# PCB_AirSENSE_v4_1_3.net
KiCad netlist of a schematic drawn in Altium Designer
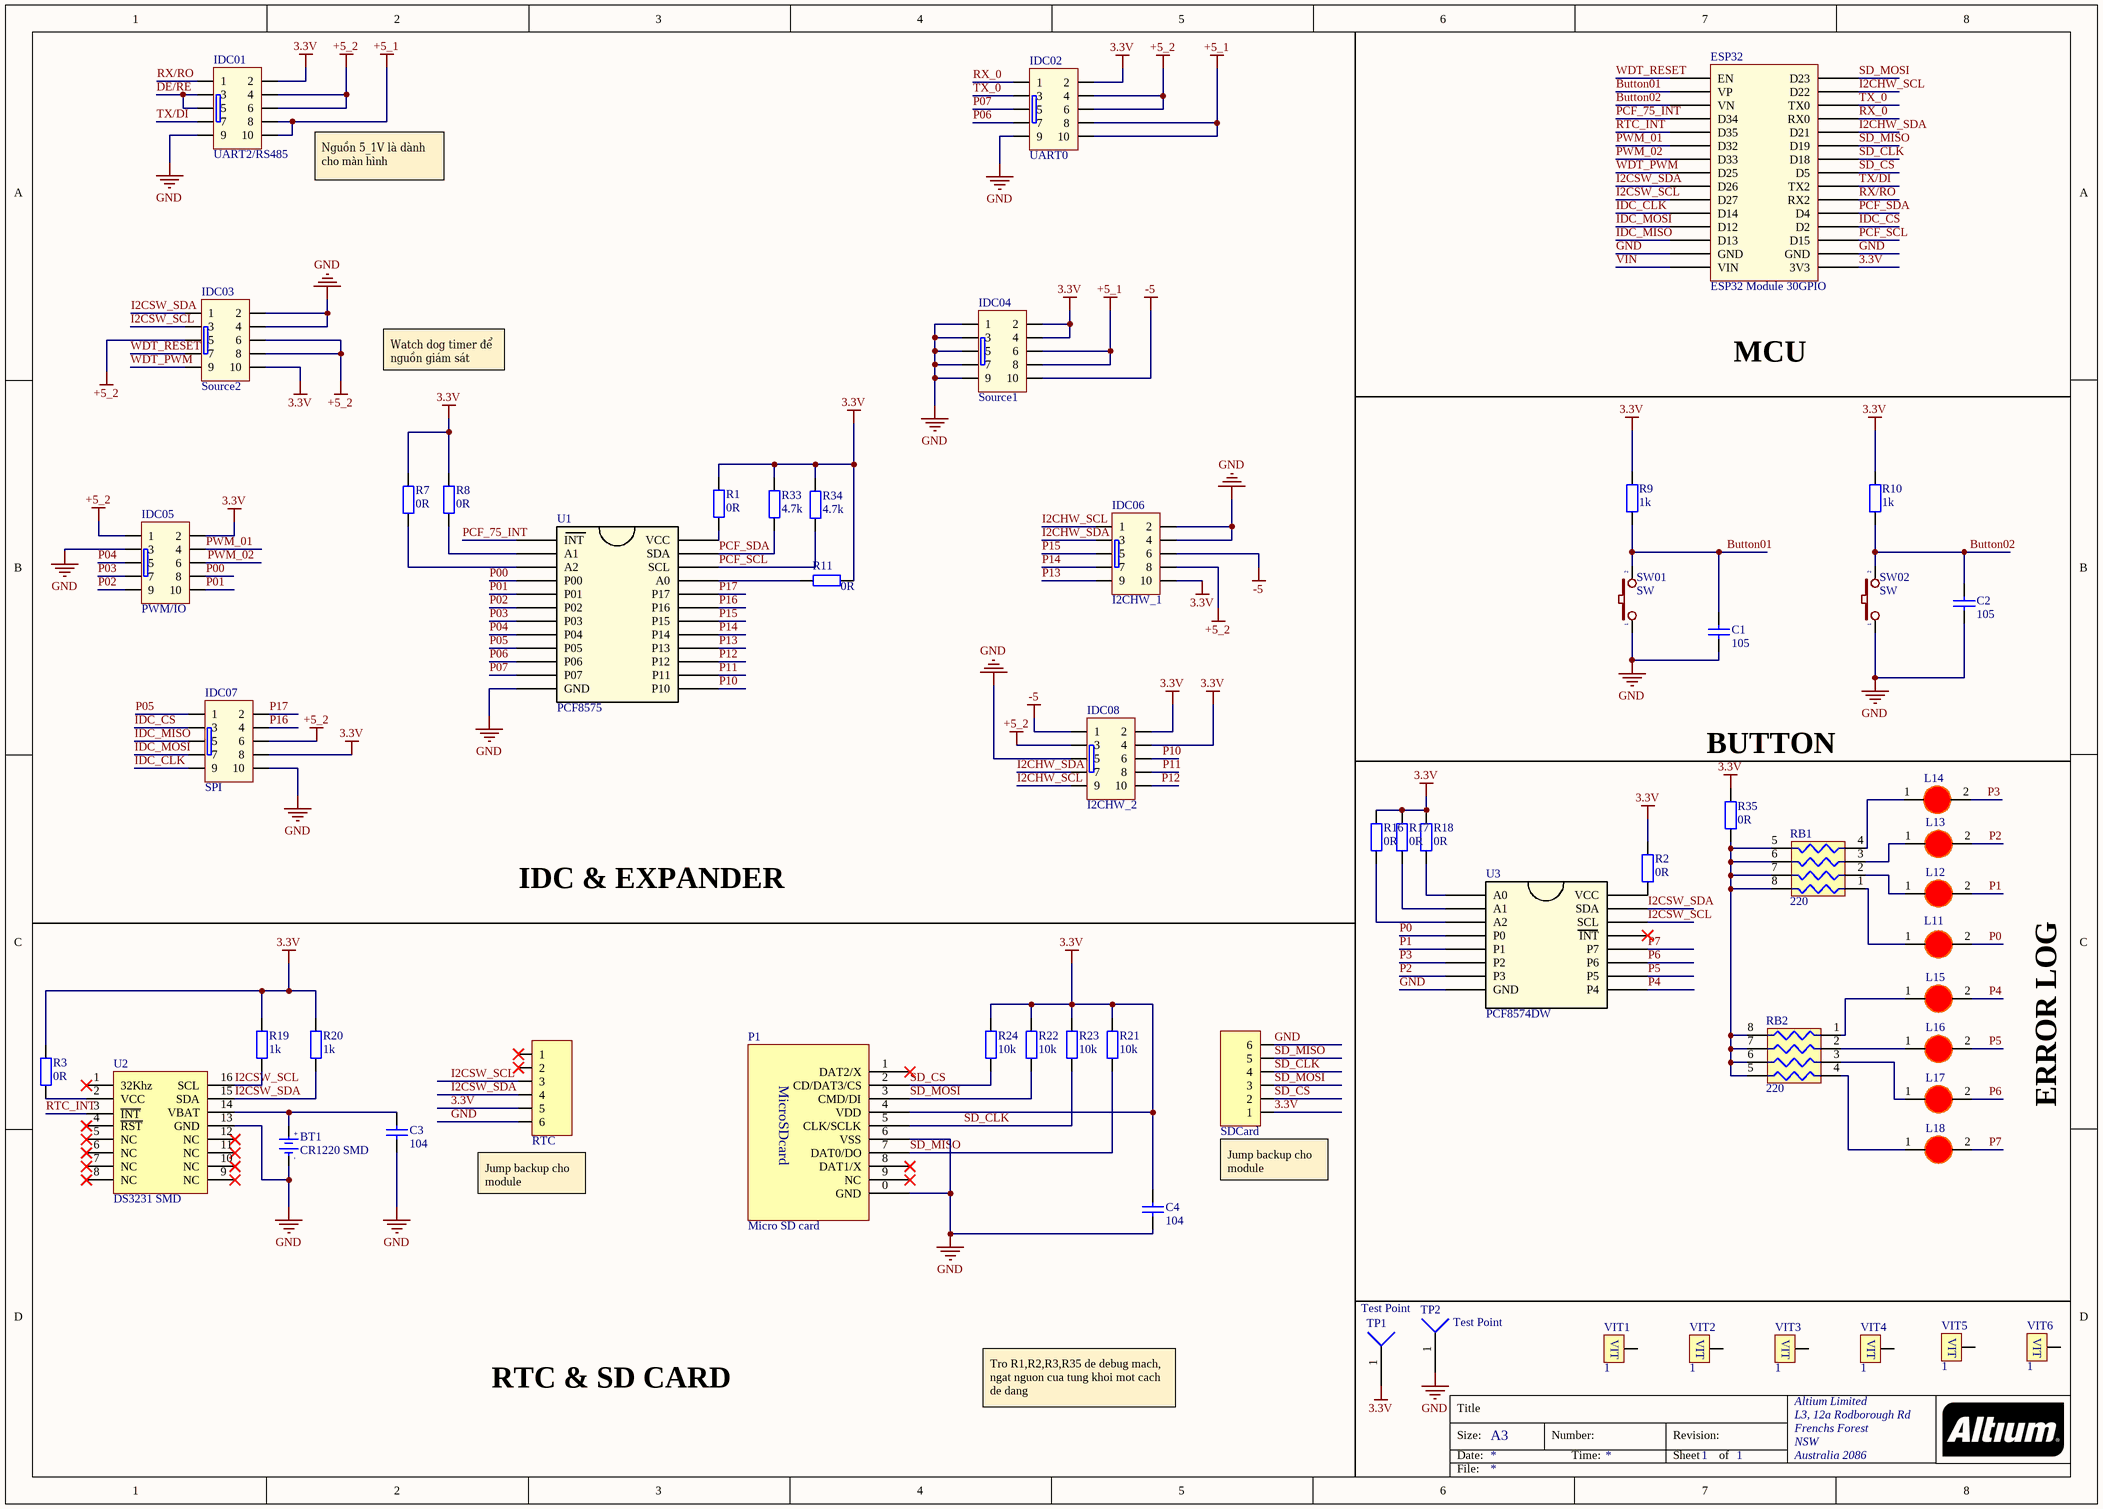
[diagram p0: PCB_AirSENSE_v4.1.3.SchDoc]

(export (version "E")
  (design (tool "Eeschema 10.0.6"))
  (components
    (comp (ref "BT1")
      (value "CR1220 SMD")
      (footprint "DE PIN CR1220")
      (libsource (lib "Component") (part "De pin CR1220 SMD"))
    )
    (comp (ref "C1")
      (value "105")
      (footprint "tu 0805")
      (description "Dán")
      (libsource (lib "Tu dien") (part "Tu 0805 105 50V 10%"))
    )
    (comp (ref "C2")
      (value "105")
      (footprint "tu 0805")
      (description "Dán")
      (libsource (lib "Tu dien") (part "Tu 0805 105 50V 10%"))
    )
    (comp (ref "C3")
      (value "104")
      (footprint "tu 0805")
      (description "Dán")
      (libsource (lib "Tu dien") (part "Tu 0805 105 50V 10%"))
    )
    (comp (ref "C4")
      (value "104")
      (footprint "tu 0805")
      (description "Dán")
      (libsource (lib "Tu dien") (part "Tu 0805 105 50V 10%"))
    )
    (comp (ref "ESP32")
      (value "ESP32 Module 30GPIO")
      (footprint "ESP32 Module 30GPIO_v3")
      (libsource (lib "Module1") (part "ESP32 Module 30GPIO"))
    )
    (comp (ref "IDC01")
      (value "UART2/RS485")
      (footprint "IDC10")
      (libsource (lib "LIBRARY") (part "IDC 5X2"))
    )
    (comp (ref "IDC02") (value "UART0") (footprint "IDC10") (libsource (lib "LIBRARY") (part "IDC 5X2")))
    (comp (ref "IDC03") (value "Source2") (footprint "IDC10") (libsource (lib "LIBRARY") (part "IDC 5X2")))
    (comp (ref "IDC04") (value "Source1") (footprint "IDC10") (libsource (lib "LIBRARY") (part "IDC 5X2")))
    (comp (ref "IDC05") (value "PWM/IO") (footprint "IDC10") (libsource (lib "LIBRARY") (part "IDC 5X2")))
    (comp (ref "IDC06") (value "I2CHW_1") (footprint "IDC10") (libsource (lib "LIBRARY") (part "IDC 5X2")))
    (comp (ref "IDC07") (value "SPI") (footprint "IDC10") (libsource (lib "LIBRARY") (part "IDC 5X2")))
    (comp (ref "IDC08") (value "I2CHW_2") (footprint "IDC10") (libsource (lib "LIBRARY") (part "IDC 5X2")))
    (comp (ref "JP3")
      (value "SDCard")
      (footprint "JP 1x6 DT")
      (description "Cắm")
      (libsource (lib "") (part "JP 1x6 2.54 Duc Thang_1"))
    )
    (comp (ref "JP4")
      (value "RTC")
      (footprint "JP 1x6 DT")
      (description "Cắm")
      (libsource (lib "Jump") (part "JP 1x6 2.54 Duc Thang"))
    )
    (comp (ref "L11")
      (value "LED 0805")
      (footprint "Led:LED-0805-Red")
      (description "Dán")
      (libsource (lib "Led") (part "LED 0805 Do"))
    )
    (comp (ref "L12")
      (value "LED 0805")
      (footprint "Led:LED-0805-Red")
      (description "Dán")
      (libsource (lib "Led") (part "LED 0805 Do"))
    )
    (comp (ref "L13")
      (value "LED 0805")
      (footprint "Led:LED-0805-Red")
      (description "Dán")
      (libsource (lib "Led") (part "LED 0805 Do"))
    )
    (comp (ref "L14")
      (value "LED 0805")
      (footprint "Led:LED-0805-Red")
      (description "Dán")
      (libsource (lib "Led") (part "LED 0805 Do"))
    )
    (comp (ref "L15")
      (value "LED 0805")
      (footprint "Led:LED-0805-Red")
      (description "Dán")
      (libsource (lib "Led") (part "LED 0805 Do"))
    )
    (comp (ref "L16")
      (value "LED 0805")
      (footprint "Led:LED-0805-Red")
      (description "Dán")
      (libsource (lib "Led") (part "LED 0805 Do"))
    )
    (comp (ref "L17")
      (value "LED 0805")
      (footprint "Led:LED-0805-Red")
      (description "Dán")
      (libsource (lib "Led") (part "LED 0805 Do"))
    )
    (comp (ref "L18")
      (value "LED 0805")
      (footprint "Led:LED-0805-Red")
      (description "Dán")
      (libsource (lib "Led") (part "LED 0805 Do"))
    )
    (comp (ref "P1")
      (value "Micro SD card")
      (footprint "MicroSD")
      (libsource (lib "Component") (part "Micro SD card"))
    )
    (comp (ref "R1")
      (value "0R")
      (footprint "tro smd 0805")
      (description "Dán")
      (libsource (lib "Dien Tro") (part "Tro 0805 5% 0R"))
    )
    (comp (ref "R2")
      (value "0R")
      (footprint "tro smd 0805")
      (description "Dán")
      (libsource (lib "Dien Tro") (part "Tro 0805 5% 0R"))
    )
    (comp (ref "R3")
      (value "0R")
      (footprint "tro smd 0805")
      (description "Dán")
      (libsource (lib "Dien Tro") (part "Tro 0805 5% 0R"))
    )
    (comp (ref "R7")
      (value "0R")
      (footprint "tro smd 0805")
      (description "Dán")
      (libsource (lib "Dien Tro") (part "Tro 0805 5% 0R"))
    )
    (comp (ref "R8")
      (value "0R")
      (footprint "tro smd 0805")
      (description "Dán")
      (libsource (lib "Dien Tro") (part "Tro 0805 5% 0R"))
    )
    (comp (ref "R9")
      (value "1k")
      (footprint "tro smd 0805")
      (description "Dán")
      (libsource (lib "Dien Tro") (part "Tro 0805 5% 0R"))
    )
    (comp (ref "R10")
      (value "1k")
      (footprint "tro smd 0805")
      (description "Dán")
      (libsource (lib "Dien Tro") (part "Tro 0805 5% 0R"))
    )
    (comp (ref "R11")
      (value "0R")
      (footprint "tro smd 0805")
      (description "Dán")
      (libsource (lib "Dien Tro") (part "Tro 0805 5% 0R"))
    )
    (comp (ref "R16")
      (value "0R")
      (footprint "tro smd 0805")
      (description "Dán")
      (libsource (lib "Dien Tro") (part "Tro 0805 5% 0R"))
    )
    (comp (ref "R17")
      (value "0R")
      (footprint "tro smd 0805")
      (description "Dán")
      (libsource (lib "Dien Tro") (part "Tro 0805 5% 0R"))
    )
    (comp (ref "R18")
      (value "0R")
      (footprint "tro smd 0805")
      (description "Dán")
      (libsource (lib "Dien Tro") (part "Tro 0805 5% 0R"))
    )
    (comp (ref "R19")
      (value "1k")
      (footprint "tro smd 0805")
      (description "Dán")
      (libsource (lib "Dien Tro") (part "Tro 0805 5% 1k"))
    )
    (comp (ref "R20")
      (value "1k")
      (footprint "tro smd 0805")
      (description "Dán")
      (libsource (lib "Dien Tro") (part "Tro 0805 5% 1k"))
    )
    (comp (ref "R21")
      (value "10k")
      (footprint "tro smd 0805")
      (description "Dán")
      (libsource (lib "Dien Tro") (part "Tro 0805 1% 10k"))
    )
    (comp (ref "R22")
      (value "10k")
      (footprint "tro smd 0805")
      (description "Dán")
      (libsource (lib "Dien Tro") (part "Tro 0805 1% 10k"))
    )
    (comp (ref "R23")
      (value "10k")
      (footprint "tro smd 0805")
      (description "Dán")
      (libsource (lib "Dien Tro") (part "Tro 0805 1% 10k"))
    )
    (comp (ref "R24")
      (value "10k")
      (footprint "tro smd 0805")
      (description "Dán")
      (libsource (lib "Dien Tro") (part "Tro 0805 1% 10k"))
    )
    (comp (ref "R33")
      (value "4.7k")
      (footprint "tro smd 0805")
      (description "Dán")
      (libsource (lib "Dien Tro") (part "Tro 0805 5% 4.7k"))
    )
    (comp (ref "R34")
      (value "4.7k")
      (footprint "tro smd 0805")
      (description "Dán")
      (libsource (lib "Dien Tro") (part "Tro 0805 5% 4.7k"))
    )
    (comp (ref "R35")
      (value "0R")
      (footprint "tro smd 0805")
      (description "Dán")
      (libsource (lib "Dien Tro") (part "Tro 0805 5% 0R"))
    )
    (comp (ref "RB1")
      (value "220")
      (footprint "tro bang 0603 4")
      (description "Dán")
      (libsource (lib "Dien Tro") (part "Tro bang 0603 220R"))
    )
    (comp (ref "RB2")
      (value "220")
      (footprint "tro bang 0603 4")
      (description "Dán")
      (libsource (lib "") (part "Tro bang 0603 220R_1"))
    )
    (comp (ref "SW01")
      (value "SW")
      (footprint "SW1-SMD")
      (description "Switch button 2 pin")
      (libsource (lib "LIBRARY") (part "SW2"))
    )
    (comp (ref "SW02")
      (value "SW")
      (footprint "SW1-SMD")
      (description "Switch button 2 pin")
      (libsource (lib "LIBRARY") (part "SW2"))
    )
    (comp (ref "TP1")
      (value "Test Point")
      (footprint "MinhTien_PCBLib:TEST_POINT_1.5X1.5MM")
      (fields (field (name "PUBLISHER") "Altium Limited"))
      (libsource (lib "MinhTien_SCHLib") (part "Test Point"))
    )
    (comp (ref "TP2")
      (value "Test Point")
      (footprint "MinhTien_PCBLib:TEST_POINT_1.5X1.5MM")
      (fields (field (name "PUBLISHER") "Altium Limited"))
      (libsource (lib "MinhTien_SCHLib") (part "Test Point"))
    )
    (comp (ref "U1")
      (value "PCF8575")
      (footprint "IC:SSOP65P775X200-24N")
      (description "PCF8575DW 24pins to expand I/O by I2C protocol (16bit)")
      (libsource (lib "IC") (part "PCF8575DW"))
    )
    (comp (ref "U2")
      (value "DS3231 SMD")
      (footprint "SOIC 16")
      (description "SOIC")
      (libsource (lib "IC") (part "DS3231 SMD"))
    )
    (comp (ref "U3")
      (value "PCF8574DW")
      (footprint "PCF8574DW SOIC16")
      (description "PCF8574DW 16 pins to expand I/O by I2C protocol (8bit)")
      (libsource (lib "IC") (part "PCF8574DW"))
    )
    (comp (ref "VIT1")
      (value "1")
      (footprint "VIT_3.7mm")
      (description "Oc Vit")
      (libsource (lib "lpson") (part "VIT"))
    )
    (comp (ref "VIT2")
      (value "1")
      (footprint "VIT_3.7mm")
      (description "Oc Vit")
      (libsource (lib "lpson") (part "VIT"))
    )
    (comp (ref "VIT3")
      (value "1")
      (footprint "VIT_3.7mm")
      (description "Oc Vit")
      (libsource (lib "lpson") (part "VIT"))
    )
    (comp (ref "VIT4")
      (value "1")
      (footprint "VIT_3.7mm")
      (description "Oc Vit")
      (libsource (lib "lpson") (part "VIT"))
    )
    (comp (ref "VIT5")
      (value "1")
      (footprint "VIT_3.7mm")
      (description "Oc Vit")
      (libsource (lib "lpson") (part "VIT"))
    )
    (comp (ref "VIT6")
      (value "1")
      (footprint "VIT_3.7mm")
      (description "Oc Vit")
      (libsource (lib "lpson") (part "VIT"))
    )
  )
  (nets
    (net (code "1") (name "+5_1") (class "Default")
      (node (ref "IDC01") (pin "10") (pinfunction "10_10") (pintype "passive"))
      (node (ref "IDC01") (pin "8") (pinfunction "8_8") (pintype "passive"))
      (node (ref "IDC02") (pin "10") (pinfunction "10_10") (pintype "passive"))
      (node (ref "IDC02") (pin "8") (pinfunction "8_8") (pintype "passive"))
      (node (ref "IDC04") (pin "6") (pinfunction "6_6") (pintype "passive"))
      (node (ref "IDC04") (pin "8") (pinfunction "8_8") (pintype "passive"))
    )
    (net (code "2") (name "+5_2") (class "Default")
      (node (ref "IDC01") (pin "4") (pinfunction "4_4") (pintype "passive"))
      (node (ref "IDC01") (pin "6") (pinfunction "6_6") (pintype "passive"))
      (node (ref "IDC02") (pin "4") (pinfunction "4_4") (pintype "passive"))
      (node (ref "IDC02") (pin "6") (pinfunction "6_6") (pintype "passive"))
      (node (ref "IDC03") (pin "5") (pinfunction "5_5") (pintype "passive"))
      (node (ref "IDC03") (pin "6") (pinfunction "6_6") (pintype "passive"))
      (node (ref "IDC03") (pin "8") (pinfunction "8_8") (pintype "passive"))
      (node (ref "IDC05") (pin "1") (pinfunction "1_1") (pintype "passive"))
      (node (ref "IDC06") (pin "8") (pinfunction "8_8") (pintype "passive"))
      (node (ref "IDC07") (pin "6") (pinfunction "6_6") (pintype "passive"))
      (node (ref "IDC08") (pin "3") (pinfunction "3_3") (pintype "passive"))
    )
    (net (code "3") (name "-5") (class "Default")
      (node (ref "IDC04") (pin "10") (pinfunction "10_10") (pintype "passive"))
      (node (ref "IDC06") (pin "6") (pinfunction "6_6") (pintype "passive"))
      (node (ref "IDC08") (pin "1") (pinfunction "1_1") (pintype "passive"))
    )
    (net (code "4") (name "/Button01") (class "Default")
      (node (ref "C1") (pin "1") (pinfunction "1_1") (pintype "passive"))
      (node (ref "ESP32") (pin "17") (pinfunction "VP_17") (pintype "passive"))
      (node (ref "R9") (pin "1") (pinfunction "1_1") (pintype "passive"))
      (node (ref "SW01") (pin "2") (pinfunction "2_2") (pintype "passive"))
    )
    (net (code "5") (name "/Button02") (class "Default")
      (node (ref "C2") (pin "1") (pinfunction "1_1") (pintype "passive"))
      (node (ref "ESP32") (pin "18") (pinfunction "VN_18") (pintype "passive"))
      (node (ref "R10") (pin "1") (pinfunction "1_1") (pintype "passive"))
      (node (ref "SW02") (pin "2") (pinfunction "2_2") (pintype "passive"))
    )
    (net (code "6") (name "/DE{slash}RE") (class "Default")
      (node (ref "IDC01") (pin "3") (pinfunction "3_3") (pintype "passive"))
      (node (ref "IDC01") (pin "5") (pinfunction "5_5") (pintype "passive"))
    )
    (net (code "7") (name "/I2CHW_SCL") (class "Default")
      (node (ref "ESP32") (pin "2") (pinfunction "D22_2") (pintype "passive"))
      (node (ref "IDC06") (pin "1") (pinfunction "1_1") (pintype "passive"))
      (node (ref "IDC08") (pin "9") (pinfunction "9_9") (pintype "passive"))
    )
    (net (code "8") (name "/I2CHW_SDA") (class "Default")
      (node (ref "ESP32") (pin "5") (pinfunction "D21_5") (pintype "passive"))
      (node (ref "IDC06") (pin "3") (pinfunction "3_3") (pintype "passive"))
      (node (ref "IDC08") (pin "7") (pinfunction "7_7") (pintype "passive"))
    )
    (net (code "9") (name "/I2CSW_SCL") (class "Default")
      (node (ref "ESP32") (pin "25") (pinfunction "D27_25") (pintype "passive"))
      (node (ref "IDC03") (pin "3") (pinfunction "3_3") (pintype "passive"))
      (node (ref "JP4") (pin "3") (pinfunction "3_3") (pintype "passive"))
      (node (ref "R19") (pin "1") (pinfunction "1_1") (pintype "passive"))
      (node (ref "U2") (pin "16") (pinfunction "SCL_16") (pintype "power_in"))
      (node (ref "U3") (pin "14") (pinfunction "SCL_14") (pintype "passive"))
    )
    (net (code "10") (name "/I2CSW_SDA") (class "Default")
      (node (ref "ESP32") (pin "24") (pinfunction "D26_24") (pintype "passive"))
      (node (ref "IDC03") (pin "1") (pinfunction "1_1") (pintype "passive"))
      (node (ref "JP4") (pin "4") (pinfunction "4_4") (pintype "passive"))
      (node (ref "R20") (pin "1") (pinfunction "1_1") (pintype "passive"))
      (node (ref "U2") (pin "15") (pinfunction "SDA_15") (pintype "power_in"))
      (node (ref "U3") (pin "15") (pinfunction "SDA_15") (pintype "passive"))
    )
    (net (code "11") (name "/IDC_CLK") (class "Default")
      (node (ref "ESP32") (pin "26") (pinfunction "D14_26") (pintype "passive"))
      (node (ref "IDC07") (pin "9") (pinfunction "9_9") (pintype "passive"))
    )
    (net (code "12") (name "/IDC_CS") (class "Default")
      (node (ref "ESP32") (pin "12") (pinfunction "D2_12") (pintype "passive"))
      (node (ref "IDC07") (pin "3") (pinfunction "3_3") (pintype "passive"))
    )
    (net (code "13") (name "/IDC_MISO") (class "Default")
      (node (ref "ESP32") (pin "28") (pinfunction "D13_28") (pintype "passive"))
      (node (ref "IDC07") (pin "5") (pinfunction "5_5") (pintype "passive"))
    )
    (net (code "14") (name "/IDC_MOSI") (class "Default")
      (node (ref "ESP32") (pin "27") (pinfunction "D12_27") (pintype "passive"))
      (node (ref "IDC07") (pin "7") (pinfunction "7_7") (pintype "passive"))
    )
    (net (code "15") (name "/P00") (class "Default")
      (node (ref "IDC05") (pin "8") (pinfunction "8_8") (pintype "passive"))
      (node (ref "U1") (pin "4") (pinfunction "P00_4") (pintype "passive"))
    )
    (net (code "16") (name "/P0") (class "Default")
      (node (ref "L11") (pin "2") (pinfunction "K_2") (pintype "passive"))
      (node (ref "U3") (pin "4") (pinfunction "P0_4") (pintype "passive"))
    )
    (net (code "17") (name "/P01") (class "Default")
      (node (ref "IDC05") (pin "10") (pinfunction "10_10") (pintype "passive"))
      (node (ref "U1") (pin "5") (pinfunction "P01_5") (pintype "passive"))
    )
    (net (code "18") (name "/P1") (class "Default")
      (node (ref "L12") (pin "2") (pinfunction "K_2") (pintype "passive"))
      (node (ref "U3") (pin "5") (pinfunction "P1_5") (pintype "passive"))
    )
    (net (code "19") (name "/P02") (class "Default")
      (node (ref "IDC05") (pin "9") (pinfunction "9_9") (pintype "passive"))
      (node (ref "U1") (pin "6") (pinfunction "P02_6") (pintype "passive"))
    )
    (net (code "20") (name "/P2") (class "Default")
      (node (ref "L13") (pin "2") (pinfunction "K_2") (pintype "passive"))
      (node (ref "U3") (pin "7") (pinfunction "P3_7") (pintype "passive"))
    )
    (net (code "21") (name "/P3") (class "Default")
      (node (ref "L14") (pin "2") (pinfunction "K_2") (pintype "passive"))
      (node (ref "U3") (pin "6") (pinfunction "P2_6") (pintype "passive"))
    )
    (net (code "22") (name "/P03") (class "Default")
      (node (ref "IDC05") (pin "7") (pinfunction "7_7") (pintype "passive"))
      (node (ref "U1") (pin "7") (pinfunction "P03_7") (pintype "passive"))
    )
    (net (code "23") (name "/P4") (class "Default")
      (node (ref "L15") (pin "2") (pinfunction "K_2") (pintype "passive"))
      (node (ref "U3") (pin "9") (pinfunction "P4_9") (pintype "passive"))
    )
    (net (code "24") (name "/P04") (class "Default")
      (node (ref "IDC05") (pin "5") (pinfunction "5_5") (pintype "passive"))
      (node (ref "U1") (pin "8") (pinfunction "P04_8") (pintype "passive"))
    )
    (net (code "25") (name "/P5") (class "Default")
      (node (ref "L16") (pin "2") (pinfunction "K_2") (pintype "passive"))
      (node (ref "U3") (pin "10") (pinfunction "P5_10") (pintype "passive"))
    )
    (net (code "26") (name "/P05") (class "Default")
      (node (ref "IDC07") (pin "1") (pinfunction "1_1") (pintype "passive"))
      (node (ref "U1") (pin "9") (pinfunction "P05_9") (pintype "passive"))
    )
    (net (code "27") (name "/P06") (class "Default")
      (node (ref "IDC02") (pin "7") (pinfunction "7_7") (pintype "passive"))
      (node (ref "U1") (pin "10") (pinfunction "P06_10") (pintype "passive"))
    )
    (net (code "28") (name "/P6") (class "Default")
      (node (ref "L17") (pin "2") (pinfunction "K_2") (pintype "passive"))
      (node (ref "U3") (pin "11") (pinfunction "P6_11") (pintype "passive"))
    )
    (net (code "29") (name "/P7") (class "Default")
      (node (ref "L18") (pin "2") (pinfunction "K_2") (pintype "passive"))
      (node (ref "U3") (pin "12") (pinfunction "P7_12") (pintype "passive"))
    )
    (net (code "30") (name "/P07") (class "Default")
      (node (ref "IDC02") (pin "5") (pinfunction "5_5") (pintype "passive"))
      (node (ref "U1") (pin "11") (pinfunction "P07_11") (pintype "passive"))
    )
    (net (code "31") (name "/P10") (class "Default")
      (node (ref "IDC08") (pin "6") (pinfunction "6_6") (pintype "passive"))
      (node (ref "U1") (pin "13") (pinfunction "P10_13") (pintype "passive"))
    )
    (net (code "32") (name "/P11") (class "Default")
      (node (ref "IDC08") (pin "8") (pinfunction "8_8") (pintype "passive"))
      (node (ref "U1") (pin "14") (pinfunction "P11_14") (pintype "passive"))
    )
    (net (code "33") (name "/P12") (class "Default")
      (node (ref "IDC08") (pin "10") (pinfunction "10_10") (pintype "passive"))
      (node (ref "U1") (pin "15") (pinfunction "P12_15") (pintype "passive"))
    )
    (net (code "34") (name "/P13") (class "Default")
      (node (ref "IDC06") (pin "9") (pinfunction "9_9") (pintype "passive"))
      (node (ref "U1") (pin "16") (pinfunction "P13_16") (pintype "passive"))
    )
    (net (code "35") (name "/P14") (class "Default")
      (node (ref "IDC06") (pin "7") (pinfunction "7_7") (pintype "passive"))
      (node (ref "U1") (pin "17") (pinfunction "P14_17") (pintype "passive"))
    )
    (net (code "36") (name "/P15") (class "Default")
      (node (ref "IDC06") (pin "5") (pinfunction "5_5") (pintype "passive"))
      (node (ref "U1") (pin "18") (pinfunction "P15_18") (pintype "passive"))
    )
    (net (code "37") (name "/P16") (class "Default")
      (node (ref "IDC07") (pin "4") (pinfunction "4_4") (pintype "passive"))
      (node (ref "U1") (pin "19") (pinfunction "P16_19") (pintype "passive"))
    )
    (net (code "38") (name "/P17") (class "Default")
      (node (ref "IDC07") (pin "2") (pinfunction "2_2") (pintype "passive"))
      (node (ref "U1") (pin "20") (pinfunction "P17_20") (pintype "passive"))
    )
    (net (code "39") (name "/PCF_75_INT") (class "Default")
      (node (ref "ESP32") (pin "19") (pinfunction "D34_19") (pintype "passive"))
      (node (ref "U1") (pin "1") (pinfunction "INT_1") (pintype "passive"))
    )
    (net (code "40") (name "/PCF_SCL") (class "Default")
      (node (ref "ESP32") (pin "13") (pinfunction "D15_13") (pintype "passive"))
      (node (ref "R34") (pin "1") (pinfunction "1_1") (pintype "passive"))
      (node (ref "U1") (pin "22") (pinfunction "SCL_22") (pintype "passive"))
    )
    (net (code "41") (name "/PCF_SDA") (class "Default")
      (node (ref "ESP32") (pin "11") (pinfunction "D4_11") (pintype "passive"))
      (node (ref "R33") (pin "1") (pinfunction "1_1") (pintype "passive"))
      (node (ref "U1") (pin "23") (pinfunction "SDA_23") (pintype "passive"))
    )
    (net (code "42") (name "/PWM_01") (class "Default")
      (node (ref "ESP32") (pin "21") (pinfunction "D32_21") (pintype "passive"))
      (node (ref "IDC05") (pin "4") (pinfunction "4_4") (pintype "passive"))
    )
    (net (code "43") (name "/PWM_02") (class "Default")
      (node (ref "ESP32") (pin "22") (pinfunction "D33_22") (pintype "passive"))
      (node (ref "IDC05") (pin "6") (pinfunction "6_6") (pintype "passive"))
    )
    (net (code "44") (name "/RTC_INT") (class "Default")
      (node (ref "ESP32") (pin "20") (pinfunction "D35_20") (pintype "passive"))
      (node (ref "U2") (pin "3") (pinfunction "~{INT}_3") (pintype "power_in"))
    )
    (net (code "45") (name "/RX_0") (class "Default")
      (node (ref "ESP32") (pin "4") (pinfunction "RX0_4") (pintype "passive"))
      (node (ref "IDC02") (pin "1") (pinfunction "1_1") (pintype "passive"))
    )
    (net (code "46") (name "/RX{slash}RO") (class "Default")
      (node (ref "ESP32") (pin "10") (pinfunction "RX2_10") (pintype "passive"))
      (node (ref "IDC01") (pin "1") (pinfunction "1_1") (pintype "passive"))
    )
    (net (code "47") (name "/SD_CLK") (class "Default")
      (node (ref "ESP32") (pin "7") (pinfunction "D18_7") (pintype "passive"))
      (node (ref "JP3") (pin "4") (pinfunction "4_4") (pintype "passive"))
      (node (ref "P1") (pin "5") (pinfunction "CLK/SCLK_5") (pintype "passive"))
      (node (ref "R23") (pin "1") (pinfunction "1_1") (pintype "passive"))
    )
    (net (code "48") (name "/SD_CS") (class "Default")
      (node (ref "ESP32") (pin "8") (pinfunction "D5_8") (pintype "passive"))
      (node (ref "JP3") (pin "2") (pinfunction "2_2") (pintype "passive"))
      (node (ref "P1") (pin "2") (pinfunction "CD/DAT3/CS_2") (pintype "passive"))
      (node (ref "R24") (pin "1") (pinfunction "1_1") (pintype "passive"))
    )
    (net (code "49") (name "/SD_MISO") (class "Default")
      (node (ref "ESP32") (pin "6") (pinfunction "D19_6") (pintype "passive"))
      (node (ref "JP3") (pin "5") (pinfunction "5_5") (pintype "passive"))
      (node (ref "P1") (pin "7") (pinfunction "DAT0/DO_7") (pintype "passive"))
      (node (ref "R21") (pin "1") (pinfunction "1_1") (pintype "passive"))
    )
    (net (code "50") (name "/SD_MOSI") (class "Default")
      (node (ref "ESP32") (pin "1") (pinfunction "D23_1") (pintype "passive"))
      (node (ref "JP3") (pin "3") (pinfunction "3_3") (pintype "passive"))
      (node (ref "P1") (pin "3") (pinfunction "CMD/DI_3") (pintype "passive"))
      (node (ref "R22") (pin "1") (pinfunction "1_1") (pintype "passive"))
    )
    (net (code "51") (name "/TX_0") (class "Default")
      (node (ref "ESP32") (pin "3") (pinfunction "TX0_3") (pintype "passive"))
      (node (ref "IDC02") (pin "3") (pinfunction "3_3") (pintype "passive"))
    )
    (net (code "52") (name "/TX{slash}DI") (class "Default")
      (node (ref "ESP32") (pin "9") (pinfunction "TX2_9") (pintype "passive"))
      (node (ref "IDC01") (pin "7") (pinfunction "7_7") (pintype "passive"))
    )
    (net (code "53") (name "/VIN") (class "Default")
      (node (ref "ESP32") (pin "30") (pinfunction "VIN_30") (pintype "passive"))
    )
    (net (code "54") (name "/WDT_PWM") (class "Default")
      (node (ref "ESP32") (pin "23") (pinfunction "D25_23") (pintype "passive"))
      (node (ref "IDC03") (pin "9") (pinfunction "9_9") (pintype "passive"))
    )
    (net (code "55") (name "/WDT_RESET") (class "Default")
      (node (ref "ESP32") (pin "16") (pinfunction "EN_16") (pintype "passive"))
      (node (ref "IDC03") (pin "7") (pinfunction "7_7") (pintype "passive"))
    )
    (net (code "56") (name "3.3V") (class "Default")
      (node (ref "C4") (pin "1") (pinfunction "1_1") (pintype "passive"))
      (node (ref "ESP32") (pin "15") (pinfunction "3V3_15") (pintype "passive"))
      (node (ref "IDC01") (pin "2") (pinfunction "2_2") (pintype "passive"))
      (node (ref "IDC02") (pin "2") (pinfunction "2_2") (pintype "passive"))
      (node (ref "IDC03") (pin "10") (pinfunction "10_10") (pintype "passive"))
      (node (ref "IDC04") (pin "2") (pinfunction "2_2") (pintype "passive"))
      (node (ref "IDC04") (pin "4") (pinfunction "4_4") (pintype "passive"))
      (node (ref "IDC05") (pin "2") (pinfunction "2_2") (pintype "passive"))
      (node (ref "IDC06") (pin "10") (pinfunction "10_10") (pintype "passive"))
      (node (ref "IDC07") (pin "8") (pinfunction "8_8") (pintype "passive"))
      (node (ref "IDC08") (pin "2") (pinfunction "2_2") (pintype "passive"))
      (node (ref "IDC08") (pin "4") (pinfunction "4_4") (pintype "passive"))
      (node (ref "JP3") (pin "1") (pinfunction "1_1") (pintype "passive"))
      (node (ref "JP4") (pin "5") (pinfunction "5_5") (pintype "passive"))
      (node (ref "P1") (pin "4") (pinfunction "VDD_4") (pintype "passive"))
      (node (ref "R1") (pin "2") (pinfunction "2_2") (pintype "passive"))
      (node (ref "R10") (pin "2") (pinfunction "2_2") (pintype "passive"))
      (node (ref "R11") (pin "2") (pinfunction "2_2") (pintype "passive"))
      (node (ref "R16") (pin "1") (pinfunction "1_1") (pintype "passive"))
      (node (ref "R17") (pin "1") (pinfunction "1_1") (pintype "passive"))
      (node (ref "R18") (pin "1") (pinfunction "1_1") (pintype "passive"))
      (node (ref "R19") (pin "2") (pinfunction "2_2") (pintype "passive"))
      (node (ref "R2") (pin "2") (pinfunction "2_2") (pintype "passive"))
      (node (ref "R20") (pin "2") (pinfunction "2_2") (pintype "passive"))
      (node (ref "R21") (pin "2") (pinfunction "2_2") (pintype "passive"))
      (node (ref "R22") (pin "2") (pinfunction "2_2") (pintype "passive"))
      (node (ref "R23") (pin "2") (pinfunction "2_2") (pintype "passive"))
      (node (ref "R24") (pin "2") (pinfunction "2_2") (pintype "passive"))
      (node (ref "R3") (pin "2") (pinfunction "2_2") (pintype "passive"))
      (node (ref "R33") (pin "2") (pinfunction "2_2") (pintype "passive"))
      (node (ref "R34") (pin "2") (pinfunction "2_2") (pintype "passive"))
      (node (ref "R35") (pin "1") (pinfunction "1_1") (pintype "passive"))
      (node (ref "R7") (pin "1") (pinfunction "1_1") (pintype "passive"))
      (node (ref "R8") (pin "1") (pinfunction "1_1") (pintype "passive"))
      (node (ref "R9") (pin "2") (pinfunction "2_2") (pintype "passive"))
      (node (ref "TP1") (pin "1") (pinfunction "1_1") (pintype "passive"))
    )
    (net (code "57") (name "GND") (class "Default")
      (node (ref "BT1") (pin "2") (pinfunction "GND_2") (pintype "passive"))
      (node (ref "C1") (pin "2") (pinfunction "2_2") (pintype "passive"))
      (node (ref "C2") (pin "2") (pinfunction "2_2") (pintype "passive"))
      (node (ref "C3") (pin "2") (pinfunction "2_2") (pintype "passive"))
      (node (ref "C4") (pin "2") (pinfunction "2_2") (pintype "passive"))
      (node (ref "ESP32") (pin "14") (pinfunction "GND_14") (pintype "passive"))
      (node (ref "ESP32") (pin "29") (pinfunction "GND_29") (pintype "passive"))
      (node (ref "IDC01") (pin "9") (pinfunction "9_9") (pintype "passive"))
      (node (ref "IDC02") (pin "9") (pinfunction "9_9") (pintype "passive"))
      (node (ref "IDC03") (pin "2") (pinfunction "2_2") (pintype "passive"))
      (node (ref "IDC03") (pin "4") (pinfunction "4_4") (pintype "passive"))
      (node (ref "IDC04") (pin "1") (pinfunction "1_1") (pintype "passive"))
      (node (ref "IDC04") (pin "3") (pinfunction "3_3") (pintype "passive"))
      (node (ref "IDC04") (pin "5") (pinfunction "5_5") (pintype "passive"))
      (node (ref "IDC04") (pin "7") (pinfunction "7_7") (pintype "passive"))
      (node (ref "IDC04") (pin "9") (pinfunction "9_9") (pintype "passive"))
      (node (ref "IDC05") (pin "3") (pinfunction "3_3") (pintype "passive"))
      (node (ref "IDC06") (pin "2") (pinfunction "2_2") (pintype "passive"))
      (node (ref "IDC06") (pin "4") (pinfunction "4_4") (pintype "passive"))
      (node (ref "IDC07") (pin "10") (pinfunction "10_10") (pintype "passive"))
      (node (ref "IDC08") (pin "5") (pinfunction "5_5") (pintype "passive"))
      (node (ref "JP3") (pin "6") (pinfunction "6_6") (pintype "passive"))
      (node (ref "JP4") (pin "6") (pinfunction "6_6") (pintype "passive"))
      (node (ref "P1") (pin "0") (pinfunction "GND_0") (pintype "passive"))
      (node (ref "P1") (pin "6") (pinfunction "VSS_6") (pintype "passive"))
      (node (ref "SW01") (pin "1") (pinfunction "1_1") (pintype "passive"))
      (node (ref "SW02") (pin "1") (pinfunction "1_1") (pintype "passive"))
      (node (ref "TP2") (pin "1") (pinfunction "1_1") (pintype "passive"))
      (node (ref "U1") (pin "12") (pinfunction "GND_12") (pintype "passive"))
      (node (ref "U2") (pin "13") (pinfunction "GND_13") (pintype "power_in"))
      (node (ref "U3") (pin "8") (pinfunction "GND_8") (pintype "passive"))
    )
    (net (code "58") (name "Net-(BT1-+3V)") (class "Default")
      (node (ref "BT1") (pin "1") (pinfunction "+3V_1") (pintype "passive"))
      (node (ref "C3") (pin "1") (pinfunction "1_1") (pintype "passive"))
      (node (ref "U2") (pin "14") (pinfunction "VBAT_14") (pintype "power_in"))
    )
    (net (code "59") (name "Net-(L11-A)") (class "Default")
      (node (ref "L11") (pin "1") (pinfunction "A_1") (pintype "passive"))
      (node (ref "RB1") (pin "1") (pintype "passive"))
    )
    (net (code "60") (name "Net-(L12-A)") (class "Default")
      (node (ref "L12") (pin "1") (pinfunction "A_1") (pintype "passive"))
      (node (ref "RB1") (pin "2") (pintype "passive"))
    )
    (net (code "61") (name "Net-(L13-A)") (class "Default")
      (node (ref "L13") (pin "1") (pinfunction "A_1") (pintype "passive"))
      (node (ref "RB1") (pin "3") (pintype "passive"))
    )
    (net (code "62") (name "Net-(L14-A)") (class "Default")
      (node (ref "L14") (pin "1") (pinfunction "A_1") (pintype "passive"))
      (node (ref "RB1") (pin "4") (pintype "passive"))
    )
    (net (code "63") (name "Net-(L15-A)") (class "Default")
      (node (ref "L15") (pin "1") (pinfunction "A_1") (pintype "passive"))
      (node (ref "RB2") (pin "1") (pintype "passive"))
    )
    (net (code "64") (name "Net-(L16-A)") (class "Default")
      (node (ref "L16") (pin "1") (pinfunction "A_1") (pintype "passive"))
      (node (ref "RB2") (pin "2") (pintype "passive"))
    )
    (net (code "65") (name "Net-(L17-A)") (class "Default")
      (node (ref "L17") (pin "1") (pinfunction "A_1") (pintype "passive"))
      (node (ref "RB2") (pin "3") (pintype "passive"))
    )
    (net (code "66") (name "Net-(L18-A)") (class "Default")
      (node (ref "L18") (pin "1") (pinfunction "A_1") (pintype "passive"))
      (node (ref "RB2") (pin "4") (pintype "passive"))
    )
    (net (code "67") (name "Net-(R35-Pad2)") (class "Default")
      (node (ref "R35") (pin "2") (pinfunction "2_2") (pintype "passive"))
      (node (ref "RB1") (pin "5") (pintype "passive"))
      (node (ref "RB1") (pin "6") (pintype "passive"))
      (node (ref "RB1") (pin "7") (pintype "passive"))
      (node (ref "RB1") (pin "8") (pintype "passive"))
      (node (ref "RB2") (pin "5") (pintype "passive"))
      (node (ref "RB2") (pin "6") (pintype "passive"))
      (node (ref "RB2") (pin "7") (pintype "passive"))
      (node (ref "RB2") (pin "8") (pintype "passive"))
    )
    (net (code "68") (name "Net-(U1-A0)") (class "Default")
      (node (ref "R11") (pin "1") (pinfunction "1_1") (pintype "passive"))
      (node (ref "U1") (pin "21") (pinfunction "A0_21") (pintype "passive"))
    )
    (net (code "69") (name "Net-(U1-A1)") (class "Default")
      (node (ref "R8") (pin "2") (pinfunction "2_2") (pintype "passive"))
      (node (ref "U1") (pin "2") (pinfunction "A1_2") (pintype "passive"))
    )
    (net (code "70") (name "Net-(U1-A2)") (class "Default")
      (node (ref "R7") (pin "2") (pinfunction "2_2") (pintype "passive"))
      (node (ref "U1") (pin "3") (pinfunction "A2_3") (pintype "passive"))
    )
    (net (code "71") (name "Net-(U1-VCC)") (class "Default")
      (node (ref "R1") (pin "1") (pinfunction "1_1") (pintype "passive"))
      (node (ref "U1") (pin "24") (pinfunction "VCC_24") (pintype "passive"))
    )
    (net (code "72") (name "Net-(U2-VCC)") (class "Default")
      (node (ref "R3") (pin "1") (pinfunction "1_1") (pintype "passive"))
      (node (ref "U2") (pin "2") (pinfunction "VCC_2") (pintype "power_in"))
    )
    (net (code "73") (name "Net-(U3-A0)") (class "Default")
      (node (ref "R18") (pin "2") (pinfunction "2_2") (pintype "passive"))
      (node (ref "U3") (pin "1") (pinfunction "A0_1") (pintype "passive"))
    )
    (net (code "74") (name "Net-(U3-A1)") (class "Default")
      (node (ref "R17") (pin "2") (pinfunction "2_2") (pintype "passive"))
      (node (ref "U3") (pin "2") (pinfunction "A1_2") (pintype "passive"))
    )
    (net (code "75") (name "Net-(U3-A2)") (class "Default")
      (node (ref "R16") (pin "2") (pinfunction "2_2") (pintype "passive"))
      (node (ref "U3") (pin "3") (pinfunction "A2_3") (pintype "passive"))
    )
    (net (code "76") (name "Net-(U3-VCC)") (class "Default")
      (node (ref "R2") (pin "1") (pinfunction "1_1") (pintype "passive"))
      (node (ref "U3") (pin "16") (pinfunction "VCC_16") (pintype "passive"))
    )
    (net (code "77") (name "unconnected-(JP4-Pad1)") (class "Default")
      (node (ref "JP4") (pin "1") (pinfunction "1_1") (pintype "passive+no_connect"))
    )
    (net (code "78") (name "unconnected-(JP4-Pad2)") (class "Default")
      (node (ref "JP4") (pin "2") (pinfunction "2_2") (pintype "passive+no_connect"))
    )
    (net (code "79") (name "unconnected-(P1-DAT1{slash}X-Pad8)") (class "Default")
      (node (ref "P1") (pin "8") (pinfunction "DAT1/X_8") (pintype "passive+no_connect"))
    )
    (net (code "80") (name "unconnected-(P1-DAT2{slash}X-Pad1)") (class "Default")
      (node (ref "P1") (pin "1") (pinfunction "DAT2/X_1") (pintype "passive+no_connect"))
    )
    (net (code "81") (name "unconnected-(P1-NC-Pad9)") (class "Default")
      (node (ref "P1") (pin "9") (pinfunction "NC_9") (pintype "passive+no_connect"))
    )
    (net (code "82") (name "unconnected-(U2-32Khz-Pad1)") (class "Default")
      (node (ref "U2") (pin "1") (pinfunction "32Khz_1") (pintype "power_in+no_connect"))
    )
    (net (code "83") (name "unconnected-(U2-NC-Pad5)") (class "Default")
      (node (ref "U2") (pin "5") (pinfunction "NC_5") (pintype "power_in+no_connect"))
    )
    (net (code "84") (name "unconnected-(U2-NC-Pad6)") (class "Default")
      (node (ref "U2") (pin "6") (pinfunction "NC_6") (pintype "power_in+no_connect"))
    )
    (net (code "85") (name "unconnected-(U2-NC-Pad7)") (class "Default")
      (node (ref "U2") (pin "7") (pinfunction "NC_7") (pintype "power_in+no_connect"))
    )
    (net (code "86") (name "unconnected-(U2-NC-Pad8)") (class "Default")
      (node (ref "U2") (pin "8") (pinfunction "NC_8") (pintype "power_in+no_connect"))
    )
    (net (code "87") (name "unconnected-(U2-NC-Pad9)") (class "Default")
      (node (ref "U2") (pin "9") (pinfunction "NC_9") (pintype "power_in+no_connect"))
    )
    (net (code "88") (name "unconnected-(U2-NC-Pad10)") (class "Default")
      (node (ref "U2") (pin "10") (pinfunction "NC_10") (pintype "power_in+no_connect"))
    )
    (net (code "89") (name "unconnected-(U2-NC-Pad11)") (class "Default")
      (node (ref "U2") (pin "11") (pinfunction "NC_11") (pintype "power_in+no_connect"))
    )
    (net (code "90") (name "unconnected-(U2-NC-Pad12)") (class "Default")
      (node (ref "U2") (pin "12") (pinfunction "NC_12") (pintype "power_in+no_connect"))
    )
    (net (code "91") (name "unconnected-(U2-~{RST}-Pad4)") (class "Default")
      (node (ref "U2") (pin "4") (pinfunction "~{RST}_4") (pintype "power_in+no_connect"))
    )
    (net (code "92") (name "unconnected-(U3-INT-Pad13)") (class "Default")
      (node (ref "U3") (pin "13") (pinfunction "INT_13") (pintype "passive+no_connect"))
    )
    (net (code "93") (name "unconnected-(VIT1-1-PadVIT1)") (class "Default")
      (node (ref "VIT1") (pin "VIT1") (pinfunction "1_VIT1") (pintype "passive"))
    )
    (net (code "94") (name "unconnected-(VIT2-1-PadVIT1)") (class "Default")
      (node (ref "VIT2") (pin "VIT1") (pinfunction "1_VIT1") (pintype "passive"))
    )
    (net (code "95") (name "unconnected-(VIT3-1-PadVIT1)") (class "Default")
      (node (ref "VIT3") (pin "VIT1") (pinfunction "1_VIT1") (pintype "passive"))
    )
    (net (code "96") (name "unconnected-(VIT4-1-PadVIT1)") (class "Default")
      (node (ref "VIT4") (pin "VIT1") (pinfunction "1_VIT1") (pintype "passive"))
    )
    (net (code "97") (name "unconnected-(VIT5-1-PadVIT1)") (class "Default")
      (node (ref "VIT5") (pin "VIT1") (pinfunction "1_VIT1") (pintype "passive"))
    )
    (net (code "98") (name "unconnected-(VIT6-1-PadVIT1)") (class "Default")
      (node (ref "VIT6") (pin "VIT1") (pinfunction "1_VIT1") (pintype "passive"))
    )
  )
)
